# MCU.net
KiCad netlist of a schematic drawn in Altium Designer
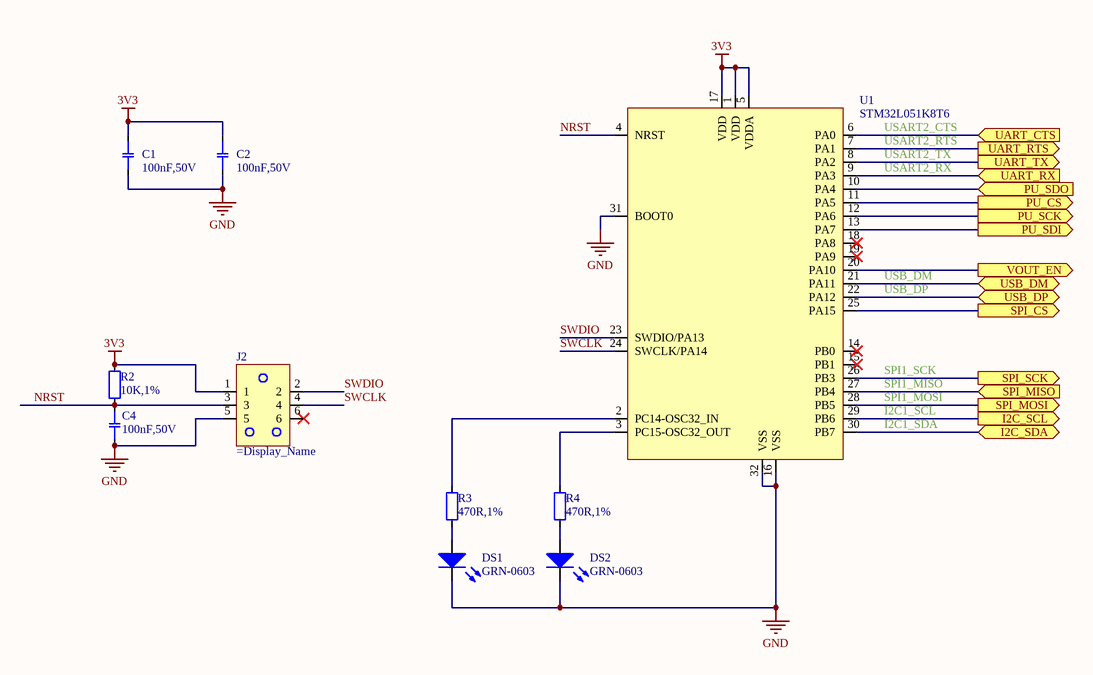
[diagram p0: MCU.SchDoc]

(export (version "E")
  (design (tool "Eeschema 10.0.6"))
  (components
    (comp (ref "C1")
      (value "100nF,50V")
      (footprint "CAPC1608X09N_0603")
      (description "CAP CER 0.1UF 50V 10% X7R 0603")
      (fields (field (name "MANUFACTURER") "Kemet") (field (name "TOLERANCE") "10%"))
      (libsource (lib "library") (part "CAP-NP_1"))
    )
    (comp (ref "C2")
      (value "100nF,50V")
      (footprint "CAPC1608X09N_0603")
      (description "CAP CER 0.1UF 50V 10% X7R 0603")
      (fields (field (name "MANUFACTURER") "Kemet") (field (name "TOLERANCE") "10%"))
      (libsource (lib "library") (part "CAP-NP_1"))
    )
    (comp (ref "C4")
      (value "100nF,50V")
      (footprint "CAPC1608X09N_0603")
      (description "CAP CER 0.1UF 50V 10% X7R 0603")
      (fields (field (name "MANUFACTURER") "Kemet") (field (name "TOLERANCE") "10%"))
      (libsource (lib "library") (part "CAP-NP_1"))
    )
    (comp (ref "DS1")
      (value "GRN-0603")
      (footprint "LED_SML-LX0603")
      (description "LED GREEN CLEAR 0603 SMD")
      (fields
        (field (name "MANUFACTURER") "Dialight")
        (field (name "MANUFACTURER PART NUMBER") "5988081107F")
      )
      (libsource (lib "library") (part "LED_1"))
    )
    (comp (ref "DS2")
      (value "GRN-0603")
      (footprint "LED_SML-LX0603")
      (description "LED GREEN CLEAR 0603 SMD")
      (fields
        (field (name "MANUFACTURER") "Dialight")
        (field (name "MANUFACTURER PART NUMBER") "5988081107F")
      )
      (libsource (lib "library") (part "LED_1"))
    )
    (comp (ref "J2")
      (value "~")
      (footprint "TAG-CONNECT_TC2030-IDC")
      (description "Tag connect 6 way")
      (libsource (lib "library") (part "TAG-CONNECT_TC2030-IDC"))
    )
    (comp (ref "R2")
      (value "10K,1%")
      (footprint "RESC1608X06N_0603")
      (description "RES 10.0K OHM 1/10W 1% 0603 SMD")
      (fields (field (name "MANUFACTURER") "Yageo") (field (name "POWER") "0.1W"))
      (libsource (lib "library") (part "RESISTOR_1"))
    )
    (comp (ref "R3")
      (value "470R,1%")
      (footprint "RESC1608X06N_0603")
      (description "RES 470 OHM 1/10W 1% 0603 SMD")
      (fields (field (name "MANUFACTURER") "Rohm Semiconductor") (field (name "POWER") "0.1W"))
      (libsource (lib "library") (part "RESISTOR_1"))
    )
    (comp (ref "R4")
      (value "470R,1%")
      (footprint "RESC1608X06N_0603")
      (description "RES 470 OHM 1/10W 1% 0603 SMD")
      (fields (field (name "MANUFACTURER") "Rohm Semiconductor") (field (name "POWER") "0.1W"))
      (libsource (lib "library") (part "RESISTOR_1"))
    )
    (comp (ref "U1")
      (value "STM32L051K8T6")
      (footprint "LQFP32")
      (description "32 Bit Mcirocontroler")
      (fields (field (name "MANUFACTURER") "ST Microelectronics"))
      (libsource (lib "library") (part "STM32L051x6/8"))
    )
  )
  (nets
    (net (code "1") (name "/I2C_SCL") (class "Default")
      (node (ref "U1") (pin "29") (pinfunction "PB6_29") (pintype "passive"))
    )
    (net (code "2") (name "/I2C_SDA") (class "Default")
      (node (ref "U1") (pin "30") (pinfunction "PB7_30") (pintype "passive"))
    )
    (net (code "3") (name "/NRST") (class "Default")
      (node (ref "C4") (pin "1") (pinfunction "1_1") (pintype "passive"))
      (node (ref "J2") (pin "3") (pinfunction "3_3") (pintype "passive"))
      (node (ref "R2") (pin "1") (pinfunction "1_1") (pintype "passive"))
      (node (ref "U1") (pin "4") (pinfunction "NRST_4") (pintype "passive"))
    )
    (net (code "4") (name "/PU_CS") (class "Default")
      (node (ref "U1") (pin "11") (pinfunction "PA5_11") (pintype "passive"))
    )
    (net (code "5") (name "/PU_SCK") (class "Default")
      (node (ref "U1") (pin "12") (pinfunction "PA6_12") (pintype "passive"))
    )
    (net (code "6") (name "/PU_SDI") (class "Default")
      (node (ref "U1") (pin "13") (pinfunction "PA7_13") (pintype "passive"))
    )
    (net (code "7") (name "/PU_SDO") (class "Default")
      (node (ref "U1") (pin "10") (pinfunction "PA4_10") (pintype "passive"))
    )
    (net (code "8") (name "/SPI_CS") (class "Default")
      (node (ref "U1") (pin "25") (pinfunction "PA15_25") (pintype "passive"))
    )
    (net (code "9") (name "/SPI_MISO") (class "Default")
      (node (ref "U1") (pin "27") (pinfunction "PB4_27") (pintype "passive"))
    )
    (net (code "10") (name "/SPI_MOSI") (class "Default")
      (node (ref "U1") (pin "28") (pinfunction "PB5_28") (pintype "passive"))
    )
    (net (code "11") (name "/SPI_SCK") (class "Default")
      (node (ref "U1") (pin "26") (pinfunction "PB3_26") (pintype "passive"))
    )
    (net (code "12") (name "/SWCLK") (class "Default")
      (node (ref "J2") (pin "4") (pinfunction "4_4") (pintype "passive"))
      (node (ref "U1") (pin "24") (pinfunction "SWCLK/PA14_24") (pintype "passive"))
    )
    (net (code "13") (name "/SWDIO") (class "Default")
      (node (ref "J2") (pin "2") (pinfunction "2_2") (pintype "passive"))
      (node (ref "U1") (pin "23") (pinfunction "SWDIO/PA13_23") (pintype "passive"))
    )
    (net (code "14") (name "/UART_CTS") (class "Default")
      (node (ref "U1") (pin "6") (pinfunction "PA0_6") (pintype "passive"))
    )
    (net (code "15") (name "/UART_RTS") (class "Default")
      (node (ref "U1") (pin "7") (pinfunction "PA1_7") (pintype "passive"))
    )
    (net (code "16") (name "/UART_RX") (class "Default")
      (node (ref "U1") (pin "9") (pinfunction "PA3_9") (pintype "passive"))
    )
    (net (code "17") (name "/UART_TX") (class "Default")
      (node (ref "U1") (pin "8") (pinfunction "PA2_8") (pintype "passive"))
    )
    (net (code "18") (name "/USB_DM") (class "Default")
      (node (ref "U1") (pin "21") (pinfunction "PA11_21") (pintype "passive"))
    )
    (net (code "19") (name "/USB_DP") (class "Default")
      (node (ref "U1") (pin "22") (pinfunction "PA12_22") (pintype "passive"))
    )
    (net (code "20") (name "/VOUT_EN") (class "Default")
      (node (ref "U1") (pin "20") (pinfunction "PA10_20") (pintype "passive"))
    )
    (net (code "21") (name "3V3") (class "Default")
      (node (ref "C1") (pin "2") (pinfunction "2_2") (pintype "passive"))
      (node (ref "C2") (pin "2") (pinfunction "2_2") (pintype "passive"))
      (node (ref "J2") (pin "1") (pinfunction "1_1") (pintype "passive"))
      (node (ref "R2") (pin "2") (pinfunction "2_2") (pintype "passive"))
      (node (ref "U1") (pin "1") (pinfunction "VDD_1") (pintype "passive"))
      (node (ref "U1") (pin "17") (pinfunction "VDD_17") (pintype "passive"))
      (node (ref "U1") (pin "5") (pinfunction "VDDA_5") (pintype "passive"))
    )
    (net (code "22") (name "GND") (class "Default")
      (node (ref "C1") (pin "1") (pinfunction "1_1") (pintype "passive"))
      (node (ref "C2") (pin "1") (pinfunction "1_1") (pintype "passive"))
      (node (ref "C4") (pin "2") (pinfunction "2_2") (pintype "passive"))
      (node (ref "DS1") (pin "1") (pinfunction "C_1") (pintype "passive"))
      (node (ref "DS2") (pin "1") (pinfunction "C_1") (pintype "passive"))
      (node (ref "J2") (pin "5") (pinfunction "5_5") (pintype "passive"))
      (node (ref "U1") (pin "16") (pinfunction "VSS_16") (pintype "passive"))
      (node (ref "U1") (pin "31") (pinfunction "BOOT0_31") (pintype "passive"))
      (node (ref "U1") (pin "32") (pinfunction "VSS_32") (pintype "passive"))
    )
    (net (code "23") (name "Net-(DS1-A)") (class "Default")
      (node (ref "DS1") (pin "2") (pinfunction "A_2") (pintype "passive"))
      (node (ref "R3") (pin "1") (pinfunction "1_1") (pintype "passive"))
    )
    (net (code "24") (name "Net-(DS2-A)") (class "Default")
      (node (ref "DS2") (pin "2") (pinfunction "A_2") (pintype "passive"))
      (node (ref "R4") (pin "1") (pinfunction "1_1") (pintype "passive"))
    )
    (net (code "25") (name "Net-(U1-PC14-OSC32_IN)") (class "Default")
      (node (ref "R3") (pin "2") (pinfunction "2_2") (pintype "passive"))
      (node (ref "U1") (pin "2") (pinfunction "PC14-OSC32_IN_2") (pintype "passive"))
    )
    (net (code "26") (name "Net-(U1-PC15-OSC32_OUT)") (class "Default")
      (node (ref "R4") (pin "2") (pinfunction "2_2") (pintype "passive"))
      (node (ref "U1") (pin "3") (pinfunction "PC15-OSC32_OUT_3") (pintype "passive"))
    )
    (net (code "27") (name "unconnected-(J2-Pad6)") (class "Default")
      (node (ref "J2") (pin "6") (pinfunction "6_6") (pintype "passive+no_connect"))
    )
    (net (code "28") (name "unconnected-(U1-PA8-Pad18)") (class "Default")
      (node (ref "U1") (pin "18") (pinfunction "PA8_18") (pintype "passive+no_connect"))
    )
    (net (code "29") (name "unconnected-(U1-PA9-Pad19)") (class "Default")
      (node (ref "U1") (pin "19") (pinfunction "PA9_19") (pintype "passive+no_connect"))
    )
    (net (code "30") (name "unconnected-(U1-PB0-Pad14)") (class "Default")
      (node (ref "U1") (pin "14") (pinfunction "PB0_14") (pintype "passive+no_connect"))
    )
    (net (code "31") (name "unconnected-(U1-PB1-Pad15)") (class "Default")
      (node (ref "U1") (pin "15") (pinfunction "PB1_15") (pintype "passive+no_connect"))
    )
  )
)
